# LED_PCB.net
KiCad netlist of a schematic drawn in Altium Designer
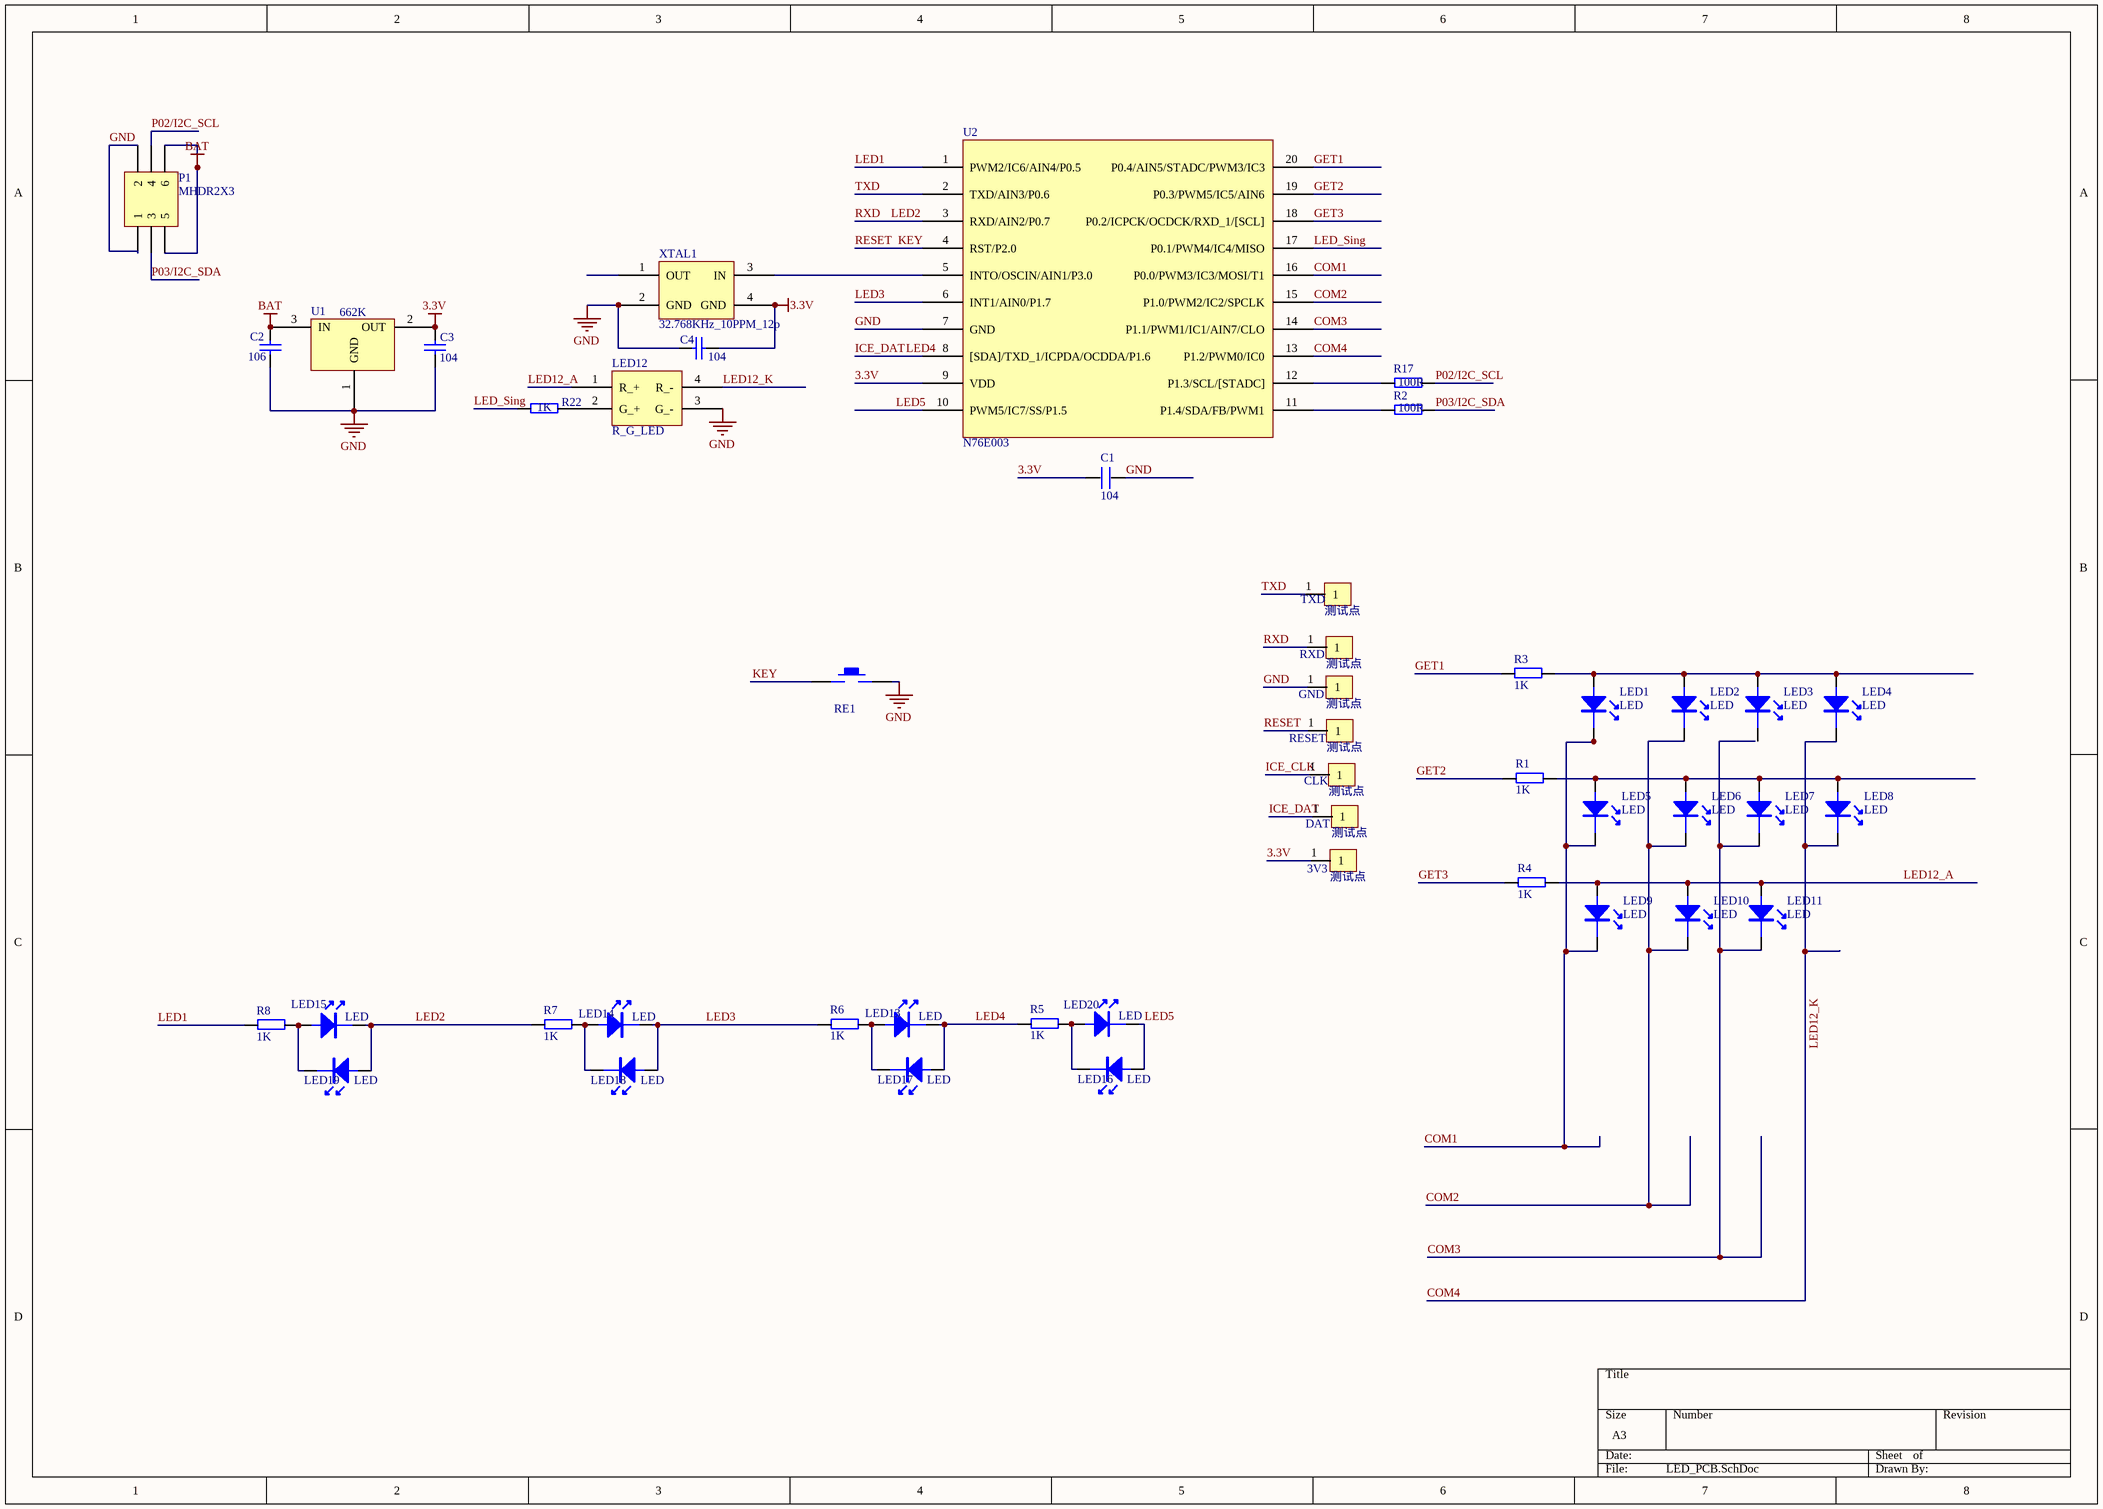
[diagram p0: LED_PCB.SchDoc]

(export (version "E")
  (design (tool "Eeschema 10.0.6"))
  (components
    (comp (ref "3V3") (value "测试点") (footprint "测试点") (libsource (lib "元件") (part "测试点")))
    (comp (ref "C1") (value "104") (footprint "0603P") (libsource (lib "3.5TFTLCD封装库") (part "C")))
    (comp (ref "C2")
      (value "106")
      (footprint "0603P")
      (description "Capacitor")
      (fields (field (name "PUBLISHER") "Altium Limited"))
      (libsource (lib "Miscellaneous Devices") (part "Cap"))
    )
    (comp (ref "C3")
      (value "104")
      (footprint "0603P")
      (description "Capacitor")
      (fields (field (name "PUBLISHER") "Altium Limited"))
      (libsource (lib "Miscellaneous Devices") (part "Cap"))
    )
    (comp (ref "C4")
      (value "104")
      (footprint "0402_C")
      (description "Capacitor")
      (fields (field (name "PUBLISHER") "Altium Limited"))
      (libsource (lib "Miscellaneous Devices") (part "Cap"))
    )
    (comp (ref "CLK") (value "测试点") (footprint "测试点") (libsource (lib "元件") (part "测试点")))
    (comp (ref "DAT") (value "测试点") (footprint "测试点") (libsource (lib "元件") (part "测试点")))
    (comp (ref "GND") (value "测试点") (footprint "测试点") (libsource (lib "元件") (part "测试点")))
    (comp (ref "LED1") (value "LED") (footprint "0402_LED") (libsource (lib "*") (part "LED")))
    (comp (ref "LED2") (value "LED") (footprint "0402_LED") (libsource (lib "*") (part "LED")))
    (comp (ref "LED3") (value "LED") (footprint "0402_LED") (libsource (lib "*") (part "LED")))
    (comp (ref "LED4") (value "LED") (footprint "0402_LED") (libsource (lib "*") (part "LED")))
    (comp (ref "LED5") (value "LED") (footprint "0402_LED") (libsource (lib "*") (part "LED")))
    (comp (ref "LED6") (value "LED") (footprint "0402_LED") (libsource (lib "*") (part "LED")))
    (comp (ref "LED7") (value "LED") (footprint "0402_LED") (libsource (lib "*") (part "LED")))
    (comp (ref "LED8") (value "LED") (footprint "0402_LED") (libsource (lib "*") (part "LED")))
    (comp (ref "LED9") (value "LED") (footprint "0402_LED") (libsource (lib "*") (part "LED")))
    (comp (ref "LED10") (value "LED") (footprint "0402_LED") (libsource (lib "*") (part "LED")))
    (comp (ref "LED11") (value "LED") (footprint "0402_LED") (libsource (lib "*") (part "LED")))
    (comp (ref "LED12") (value "R_G_LED") (footprint "0603_R_G_LED") (libsource (lib "元件") (part "R_G_LED")))
    (comp (ref "LED13") (value "LED") (footprint "0402_LED") (libsource (lib "*") (part "LED")))
    (comp (ref "LED14") (value "LED") (footprint "0402_LED") (libsource (lib "*") (part "LED")))
    (comp (ref "LED15") (value "LED") (footprint "0402_LED") (libsource (lib "*") (part "LED")))
    (comp (ref "LED16") (value "LED") (footprint "0402_LED") (libsource (lib "*") (part "LED")))
    (comp (ref "LED17") (value "LED") (footprint "0402_LED") (libsource (lib "*") (part "LED")))
    (comp (ref "LED18") (value "LED") (footprint "0402_LED") (libsource (lib "*") (part "LED")))
    (comp (ref "LED19") (value "LED") (footprint "0402_LED") (libsource (lib "*") (part "LED")))
    (comp (ref "LED20") (value "LED") (footprint "0402_LED") (libsource (lib "*") (part "LED")))
    (comp (ref "P1")
      (value "MHDR2X3")
      (footprint "AXF_6A_G")
      (description "Header, 3-Pin, Dual row")
      (fields (field (name "PUBLISHER") "Altium Limited"))
      (libsource (lib "Miscellaneous Connectors") (part "MHDR2X3"))
    )
    (comp (ref "R1")
      (value "1K")
      (footprint "自画库1:0402_R")
      (libsource (lib "Explorer STM32F407封装库") (part "R"))
    )
    (comp (ref "R2")
      (value "100R")
      (footprint "自画库1:0402_R")
      (libsource (lib "Explorer STM32F407封装库") (part "R"))
    )
    (comp (ref "R3")
      (value "1K")
      (footprint "自画库1:0402_R")
      (libsource (lib "Explorer STM32F407封装库") (part "R"))
    )
    (comp (ref "R4")
      (value "1K")
      (footprint "自画库1:0402_R")
      (libsource (lib "Explorer STM32F407封装库") (part "R"))
    )
    (comp (ref "R5")
      (value "1K")
      (footprint "自画库1:0402_R")
      (libsource (lib "Explorer STM32F407封装库") (part "R"))
    )
    (comp (ref "R6")
      (value "1K")
      (footprint "自画库1:0402_R")
      (libsource (lib "Explorer STM32F407封装库") (part "R"))
    )
    (comp (ref "R7")
      (value "1K")
      (footprint "自画库1:0402_R")
      (libsource (lib "Explorer STM32F407封装库") (part "R"))
    )
    (comp (ref "R8")
      (value "1K")
      (footprint "自画库1:0402_R")
      (libsource (lib "Explorer STM32F407封装库") (part "R"))
    )
    (comp (ref "R17")
      (value "100R")
      (footprint "自画库1:0402_R")
      (libsource (lib "Explorer STM32F407封装库") (part "R"))
    )
    (comp (ref "R22")
      (value "1K")
      (footprint "自画库1:0402_R")
      (libsource (lib "Explorer STM32F407封装库") (part "R"))
    )
    (comp (ref "RE1")
      (value "KEY_M")
      (footprint "轻触开关 2x4")
      (libsource (lib "Explorer STM32F407封装库") (part "KEY_M"))
    )
    (comp (ref "RESET") (value "测试点") (footprint "测试点") (libsource (lib "元件") (part "测试点")))
    (comp (ref "RXD") (value "测试点") (footprint "测试点") (libsource (lib "元件") (part "测试点")))
    (comp (ref "TXD") (value "测试点") (footprint "测试点") (libsource (lib "元件") (part "测试点")))
    (comp (ref "U1") (value "662K") (footprint "SOT-23") (libsource (lib "元件") (part "662K")))
    (comp (ref "U2") (value "N76E003") (footprint "STSOP20") (libsource (lib "元件") (part "N76E003")))
    (comp (ref "XTAL1")
      (value "32.768KHz_10PPM_12p")
      (footprint "晶振2*2.6")
      (libsource (lib "元件") (part "晶振"))
    )
  )
  (nets
    (net (code "1") (name "/COM1") (class "Default")
      (node (ref "LED1") (pin "2") (pinfunction "K_2") (pintype "passive"))
      (node (ref "LED5") (pin "2") (pinfunction "K_2") (pintype "passive"))
      (node (ref "LED9") (pin "2") (pinfunction "K_2") (pintype "passive"))
      (node (ref "U2") (pin "16") (pinfunction "P0.0/PWM3/IC3/MOSI/T1_16") (pintype "passive"))
    )
    (net (code "2") (name "/COM2") (class "Default")
      (node (ref "LED10") (pin "2") (pinfunction "K_2") (pintype "passive"))
      (node (ref "LED2") (pin "2") (pinfunction "K_2") (pintype "passive"))
      (node (ref "LED6") (pin "2") (pinfunction "K_2") (pintype "passive"))
      (node (ref "U2") (pin "15") (pinfunction "P1.0/PWM2/IC2/SPCLK_15") (pintype "passive"))
    )
    (net (code "3") (name "/COM3") (class "Default")
      (node (ref "LED11") (pin "2") (pinfunction "K_2") (pintype "passive"))
      (node (ref "LED7") (pin "2") (pinfunction "K_2") (pintype "passive"))
      (node (ref "U2") (pin "14") (pinfunction "P1.1/PWM1/IC1/AIN7/CLO_14") (pintype "passive"))
    )
    (net (code "4") (name "/COM4") (class "Default")
      (node (ref "LED12") (pin "4") (pinfunction "R_-_4") (pintype "passive"))
      (node (ref "LED4") (pin "2") (pinfunction "K_2") (pintype "passive"))
      (node (ref "LED8") (pin "2") (pinfunction "K_2") (pintype "passive"))
      (node (ref "U2") (pin "13") (pinfunction "P1.2/PWM0/IC0_13") (pintype "passive"))
    )
    (net (code "5") (name "/GET1") (class "Default")
      (node (ref "R3") (pin "2") (pintype "passive"))
      (node (ref "U2") (pin "20") (pinfunction "P0.4/AIN5/STADC/PWM3/IC3_20") (pintype "passive"))
    )
    (net (code "6") (name "/GET2") (class "Default")
      (node (ref "R1") (pin "2") (pintype "passive"))
      (node (ref "U2") (pin "19") (pinfunction "P0.3/PWM5/IC5/AIN6_19") (pintype "passive"))
    )
    (net (code "7") (name "/GET3") (class "Default")
      (node (ref "R4") (pin "2") (pintype "passive"))
      (node (ref "U2") (pin "18") (pinfunction "P0.2/ICPCK/OCDCK/RXD_1/[SCL]_18") (pintype "passive"))
    )
    (net (code "8") (name "/ICE_CLK") (class "Default")
      (node (ref "CLK") (pin "1") (pinfunction "1_1") (pintype "passive"))
    )
    (net (code "9") (name "/ICE_DAT") (class "Default")
      (node (ref "DAT") (pin "1") (pinfunction "1_1") (pintype "passive"))
      (node (ref "LED13") (pin "2") (pinfunction "K_2") (pintype "passive"))
      (node (ref "LED17") (pin "1") (pinfunction "A_1") (pintype "passive"))
      (node (ref "R5") (pin "2") (pintype "passive"))
      (node (ref "U2") (pin "8") (pinfunction "[SDA]/TXD_1/ICPDA/OCDDA/P1.6_8") (pintype "passive"))
    )
    (net (code "10") (name "/KEY") (class "Default")
      (node (ref "RE1") (pin "1") (pinfunction "1_1") (pintype "passive"))
      (node (ref "RESET") (pin "1") (pinfunction "1_1") (pintype "passive"))
      (node (ref "U2") (pin "4") (pinfunction "RST/P2.0_4") (pintype "passive"))
    )
    (net (code "11") (name "/LED1") (class "Default")
      (node (ref "R8") (pin "2") (pintype "passive"))
      (node (ref "U2") (pin "1") (pinfunction "PWM2/IC6/AIN4/P0.5_1") (pintype "passive"))
    )
    (net (code "12") (name "/LED2") (class "Default")
      (node (ref "LED15") (pin "2") (pinfunction "K_2") (pintype "passive"))
      (node (ref "LED19") (pin "1") (pinfunction "A_1") (pintype "passive"))
      (node (ref "R7") (pin "2") (pintype "passive"))
      (node (ref "RXD") (pin "1") (pinfunction "1_1") (pintype "passive"))
      (node (ref "U2") (pin "3") (pinfunction "RXD/AIN2/P0.7_3") (pintype "passive"))
    )
    (net (code "13") (name "/LED3") (class "Default")
      (node (ref "LED14") (pin "2") (pinfunction "K_2") (pintype "passive"))
      (node (ref "LED18") (pin "1") (pinfunction "A_1") (pintype "passive"))
      (node (ref "R6") (pin "2") (pintype "passive"))
      (node (ref "U2") (pin "6") (pinfunction "INT1/AIN0/P1.7_6") (pintype "passive"))
    )
    (net (code "14") (name "/LED5") (class "Default")
      (node (ref "LED16") (pin "1") (pinfunction "A_1") (pintype "passive"))
      (node (ref "LED20") (pin "2") (pinfunction "K_2") (pintype "passive"))
      (node (ref "U2") (pin "10") (pinfunction "PWM5/IC7/SS/P1.5_10") (pintype "passive"))
    )
    (net (code "15") (name "/LED12_A") (class "Default")
      (node (ref "LED10") (pin "1") (pinfunction "A_1") (pintype "passive"))
      (node (ref "LED11") (pin "1") (pinfunction "A_1") (pintype "passive"))
      (node (ref "LED12") (pin "1") (pinfunction "R_+_1") (pintype "passive"))
      (node (ref "LED9") (pin "1") (pinfunction "A_1") (pintype "passive"))
      (node (ref "R4") (pin "1") (pintype "passive"))
    )
    (net (code "16") (name "/LED_Sing") (class "Default")
      (node (ref "R22") (pin "2") (pintype "passive"))
      (node (ref "U2") (pin "17") (pinfunction "P0.1/PWM4/IC4/MISO_17") (pintype "passive"))
    )
    (net (code "17") (name "/P02{slash}I2C_SCL") (class "Default")
      (node (ref "P1") (pin "4") (pinfunction "4_4") (pintype "passive"))
      (node (ref "R17") (pin "1") (pintype "passive"))
    )
    (net (code "18") (name "/P03{slash}I2C_SDA") (class "Default")
      (node (ref "P1") (pin "3") (pinfunction "3_3") (pintype "passive"))
      (node (ref "R2") (pin "1") (pintype "passive"))
    )
    (net (code "19") (name "/TXD") (class "Default")
      (node (ref "TXD") (pin "1") (pinfunction "1_1") (pintype "passive"))
      (node (ref "U2") (pin "2") (pinfunction "TXD/AIN3/P0.6_2") (pintype "passive"))
    )
    (net (code "20") (name "3.3V") (class "Default")
      (node (ref "3V3") (pin "1") (pinfunction "1_1") (pintype "passive"))
      (node (ref "C1") (pin "2") (pintype "passive"))
      (node (ref "C3") (pin "2") (pinfunction "2_2") (pintype "passive"))
      (node (ref "C4") (pin "1") (pinfunction "1_1") (pintype "passive"))
      (node (ref "U1") (pin "2") (pinfunction "OUT_2") (pintype "passive"))
      (node (ref "U2") (pin "9") (pinfunction "VDD_9") (pintype "passive"))
      (node (ref "XTAL1") (pin "4") (pinfunction "GND_4") (pintype "passive"))
    )
    (net (code "21") (name "BAT") (class "Default")
      (node (ref "C2") (pin "2") (pinfunction "2_2") (pintype "passive"))
      (node (ref "P1") (pin "5") (pinfunction "5_5") (pintype "passive"))
      (node (ref "P1") (pin "6") (pinfunction "6_6") (pintype "passive"))
      (node (ref "U1") (pin "3") (pinfunction "IN_3") (pintype "passive"))
    )
    (net (code "22") (name "GND") (class "Default")
      (node (ref "C1") (pin "1") (pintype "passive"))
      (node (ref "C2") (pin "1") (pinfunction "1_1") (pintype "passive"))
      (node (ref "C3") (pin "1") (pinfunction "1_1") (pintype "passive"))
      (node (ref "C4") (pin "2") (pinfunction "2_2") (pintype "passive"))
      (node (ref "GND") (pin "1") (pinfunction "1_1") (pintype "passive"))
      (node (ref "LED12") (pin "3") (pinfunction "G_-_3") (pintype "passive"))
      (node (ref "P1") (pin "1") (pinfunction "1_1") (pintype "passive"))
      (node (ref "P1") (pin "2") (pinfunction "2_2") (pintype "passive"))
      (node (ref "RE1") (pin "2") (pinfunction "2_2") (pintype "passive"))
      (node (ref "U1") (pin "1") (pinfunction "GND_1") (pintype "passive"))
      (node (ref "U2") (pin "7") (pinfunction "GND_7") (pintype "passive"))
      (node (ref "XTAL1") (pin "2") (pinfunction "GND_2") (pintype "passive"))
    )
    (net (code "23") (name "Net-(LED1-A)") (class "Default")
      (node (ref "LED1") (pin "1") (pinfunction "A_1") (pintype "passive"))
      (node (ref "LED2") (pin "1") (pinfunction "A_1") (pintype "passive"))
      (node (ref "LED3") (pin "1") (pinfunction "A_1") (pintype "passive"))
      (node (ref "LED4") (pin "1") (pinfunction "A_1") (pintype "passive"))
      (node (ref "R3") (pin "1") (pintype "passive"))
    )
    (net (code "24") (name "Net-(LED5-A)") (class "Default")
      (node (ref "LED5") (pin "1") (pinfunction "A_1") (pintype "passive"))
      (node (ref "LED6") (pin "1") (pinfunction "A_1") (pintype "passive"))
      (node (ref "LED7") (pin "1") (pinfunction "A_1") (pintype "passive"))
      (node (ref "LED8") (pin "1") (pinfunction "A_1") (pintype "passive"))
      (node (ref "R1") (pin "1") (pintype "passive"))
    )
    (net (code "25") (name "Net-(LED12-G_+)") (class "Default")
      (node (ref "LED12") (pin "2") (pinfunction "G_+_2") (pintype "passive"))
      (node (ref "R22") (pin "1") (pintype "passive"))
    )
    (net (code "26") (name "Net-(LED13-A)") (class "Default")
      (node (ref "LED13") (pin "1") (pinfunction "A_1") (pintype "passive"))
      (node (ref "LED17") (pin "2") (pinfunction "K_2") (pintype "passive"))
      (node (ref "R6") (pin "1") (pintype "passive"))
    )
    (net (code "27") (name "Net-(LED14-A)") (class "Default")
      (node (ref "LED14") (pin "1") (pinfunction "A_1") (pintype "passive"))
      (node (ref "LED18") (pin "2") (pinfunction "K_2") (pintype "passive"))
      (node (ref "R7") (pin "1") (pintype "passive"))
    )
    (net (code "28") (name "Net-(LED15-A)") (class "Default")
      (node (ref "LED15") (pin "1") (pinfunction "A_1") (pintype "passive"))
      (node (ref "LED19") (pin "2") (pinfunction "K_2") (pintype "passive"))
      (node (ref "R8") (pin "1") (pintype "passive"))
    )
    (net (code "29") (name "Net-(LED16-K)") (class "Default")
      (node (ref "LED16") (pin "2") (pinfunction "K_2") (pintype "passive"))
      (node (ref "LED20") (pin "1") (pinfunction "A_1") (pintype "passive"))
      (node (ref "R5") (pin "1") (pintype "passive"))
    )
    (net (code "30") (name "Net-(U2-INTO{slash}OSCIN{slash}AIN1{slash}P3.0)") (class "Default")
      (node (ref "U2") (pin "5") (pinfunction "INTO/OSCIN/AIN1/P3.0_5") (pintype "passive"))
      (node (ref "XTAL1") (pin "3") (pinfunction "IN_3") (pintype "passive"))
    )
    (net (code "31") (name "Net-(U2-P1.3{slash}SCL{slash}[STADC])") (class "Default")
      (node (ref "R17") (pin "2") (pintype "passive"))
      (node (ref "U2") (pin "12") (pinfunction "P1.3/SCL/[STADC]_12") (pintype "passive"))
    )
    (net (code "32") (name "Net-(U2-P1.4{slash}SDA{slash}FB{slash}PWM1)") (class "Default")
      (node (ref "R2") (pin "2") (pintype "passive"))
      (node (ref "U2") (pin "11") (pinfunction "P1.4/SDA/FB/PWM1_11") (pintype "passive"))
    )
    (net (code "33") (name "unconnected-(LED3-K-Pad2)") (class "Default")
      (node (ref "LED3") (pin "2") (pinfunction "K_2") (pintype "passive"))
    )
    (net (code "34") (name "unconnected-(XTAL1-OUT-Pad1)") (class "Default")
      (node (ref "XTAL1") (pin "1") (pinfunction "OUT_1") (pintype "passive"))
    )
  )
)
